# dip.net
KiCad netlist of a schematic drawn in EAGLE
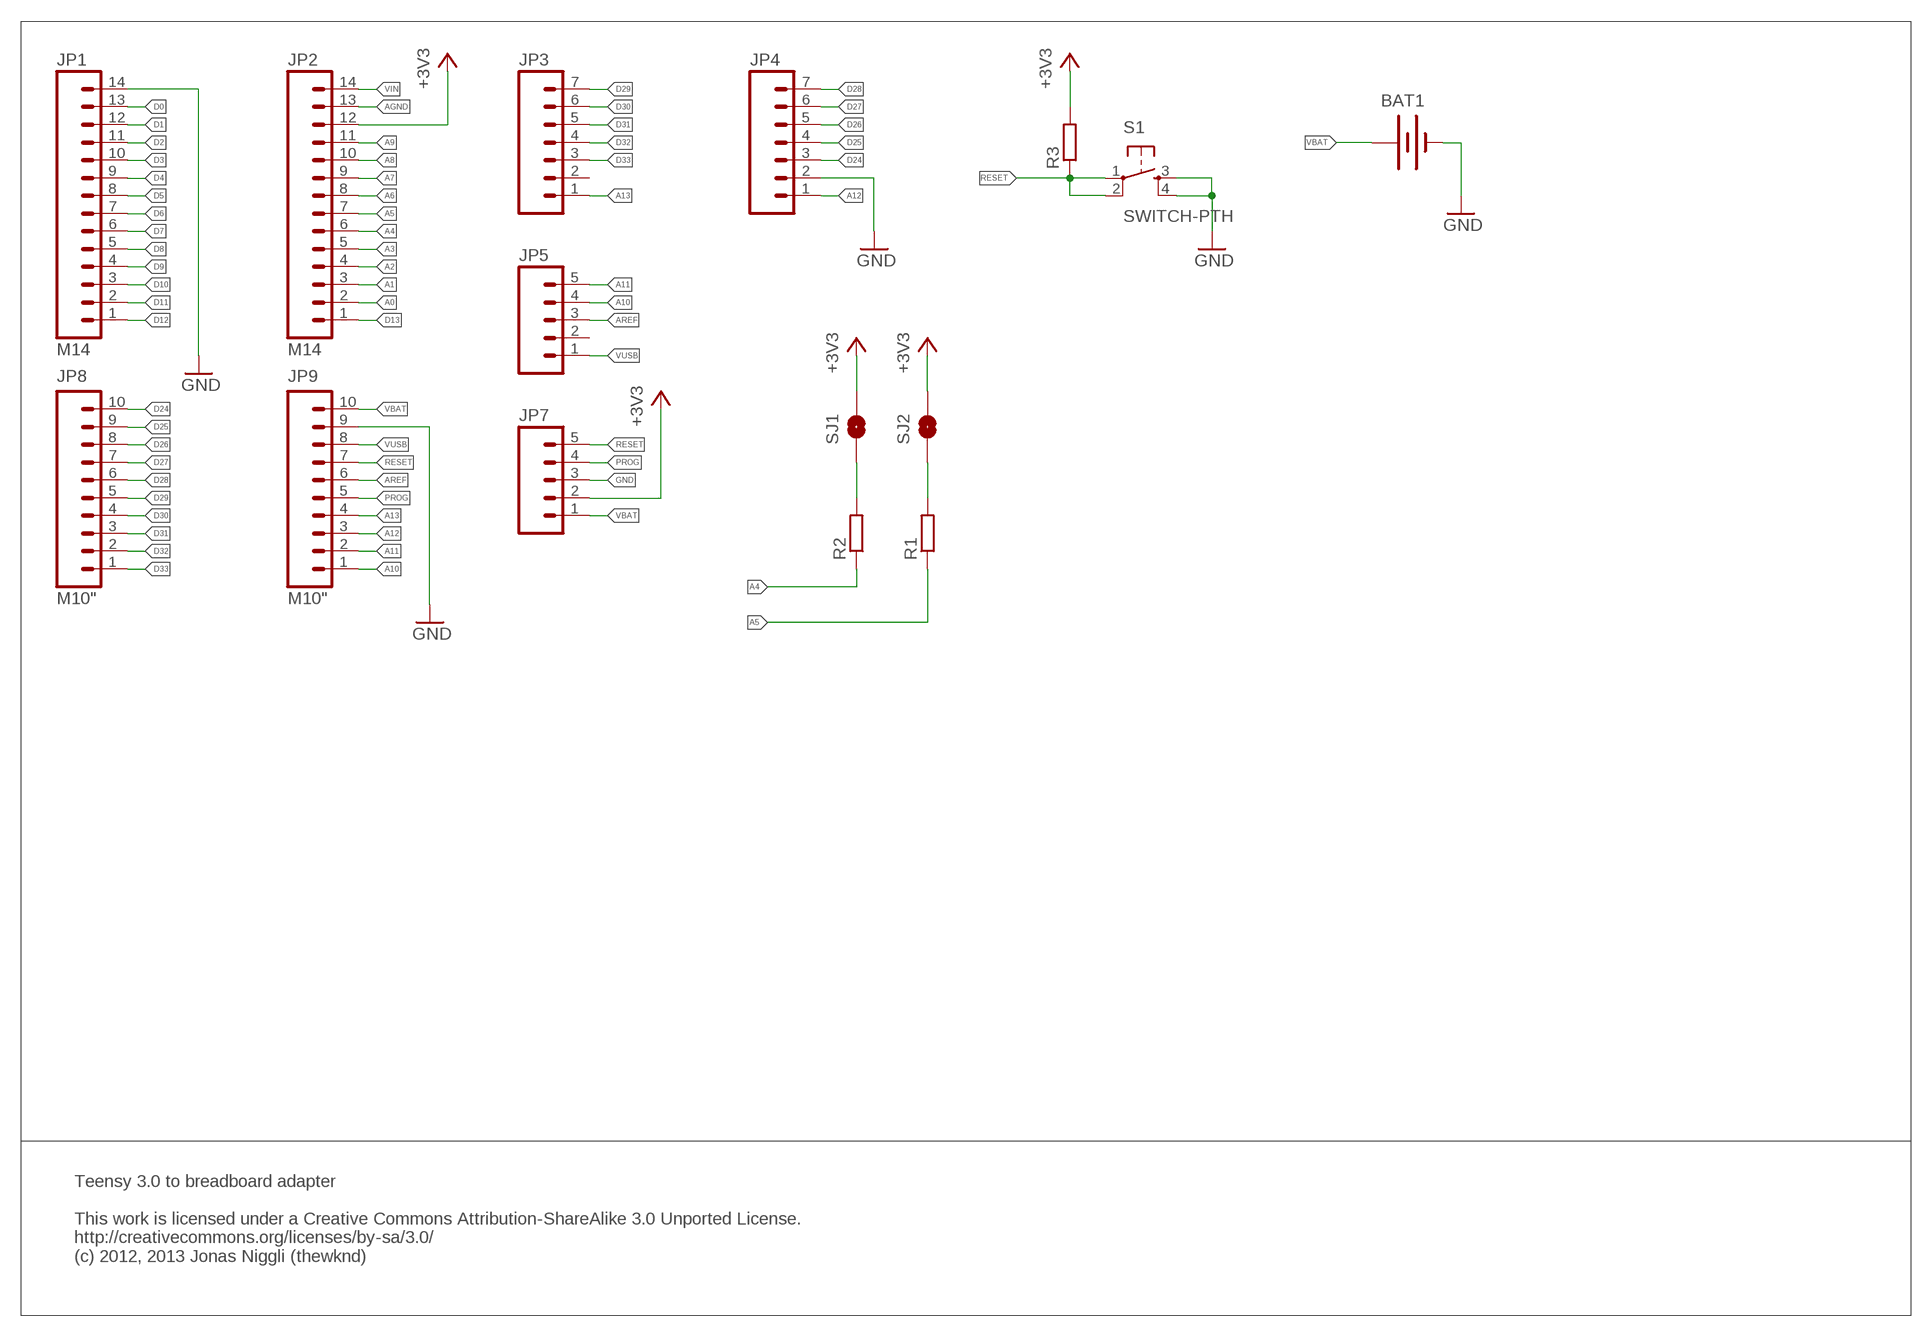
[diagram p0: schematic, sheet 1]

(export (version "E")
  (design (tool "Eeschema 10.0.6"))
  (components
    (comp (ref "BAT1")
      (value "BATTERY12MM")
      (footprint "eagle-import:BATTCON_12MM")
      (libsource (lib "eagle-import") (part "BATTERY12MM"))
    )
    (comp (ref "JP1")
      (value "M14")
      (footprint "eagle-import:1X14")
      (libsource (lib "eagle-import") (part "M14"))
    )
    (comp (ref "JP2")
      (value "M14")
      (footprint "eagle-import:1X14")
      (libsource (lib "eagle-import") (part "M14"))
    )
    (comp (ref "JP3")
      (value "M07")
      (footprint "eagle-import:1X07")
      (libsource (lib "eagle-import") (part "M07"))
    )
    (comp (ref "JP4")
      (value "M07")
      (footprint "eagle-import:1X07")
      (libsource (lib "eagle-import") (part "M07"))
    )
    (comp (ref "JP5")
      (value "M05PTH")
      (footprint "eagle-import:1X05")
      (libsource (lib "eagle-import") (part "M05PTH"))
    )
    (comp (ref "JP7")
      (value "M05PTH")
      (footprint "eagle-import:1X05")
      (libsource (lib "eagle-import") (part "M05PTH"))
    )
    (comp (ref "JP8")
      (value "M10\"")
      (footprint "eagle-import:1X10")
      (libsource (lib "eagle-import") (part "M10{dblquote}"))
    )
    (comp (ref "JP9")
      (value "M10\"")
      (footprint "eagle-import:1X10")
      (libsource (lib "eagle-import") (part "M10{dblquote}"))
    )
    (comp (ref "R1")
      (value "RESISTOR")
      (footprint "eagle-import:R0805")
      (libsource (lib "eagle-import") (part "RESISTOR"))
    )
    (comp (ref "R2")
      (value "RESISTOR")
      (footprint "eagle-import:R0805")
      (libsource (lib "eagle-import") (part "RESISTOR"))
    )
    (comp (ref "R3")
      (value "RESISTOR")
      (footprint "eagle-import:R0805")
      (libsource (lib "eagle-import") (part "RESISTOR"))
    )
    (comp (ref "S1")
      (value "SWITCH-PTH")
      (footprint "eagle-import:SWITCH_PTH")
      (libsource (lib "eagle-import") (part "SWITCH-PTH"))
    )
    (comp (ref "SJ1")
      (value "SOLDERJUMPERNO")
      (footprint "eagle-import:SJ_2S-NO")
      (libsource (lib "eagle-import") (part "SOLDERJUMPERNO"))
    )
    (comp (ref "SJ2")
      (value "SOLDERJUMPERNO")
      (footprint "eagle-import:SJ_2S-NO")
      (libsource (lib "eagle-import") (part "SOLDERJUMPERNO"))
    )
  )
  (nets
    (net (code "1") (name "+3V3") (class "Default")
      (node (ref "JP2") (pin "12") (pinfunction "12_12") (pintype "passive"))
      (node (ref "JP7") (pin "2") (pinfunction "2_2") (pintype "passive"))
      (node (ref "R3") (pin "2") (pinfunction "2_2") (pintype "passive"))
      (node (ref "SJ1") (pin "2") (pinfunction "2_2") (pintype "passive"))
      (node (ref "SJ2") (pin "2") (pinfunction "2_2") (pintype "passive"))
    )
    (net (code "2") (name "A0") (class "Default")
      (node (ref "JP2") (pin "2") (pinfunction "2_2") (pintype "passive"))
    )
    (net (code "3") (name "A1") (class "Default")
      (node (ref "JP2") (pin "3") (pinfunction "3_3") (pintype "passive"))
    )
    (net (code "4") (name "A2") (class "Default")
      (node (ref "JP2") (pin "4") (pinfunction "4_4") (pintype "passive"))
    )
    (net (code "5") (name "A3") (class "Default")
      (node (ref "JP2") (pin "5") (pinfunction "5_5") (pintype "passive"))
    )
    (net (code "6") (name "A4") (class "Default")
      (node (ref "JP2") (pin "6") (pinfunction "6_6") (pintype "passive"))
      (node (ref "R2") (pin "1") (pinfunction "1_1") (pintype "passive"))
    )
    (net (code "7") (name "A5") (class "Default")
      (node (ref "JP2") (pin "7") (pinfunction "7_7") (pintype "passive"))
      (node (ref "R1") (pin "1") (pinfunction "1_1") (pintype "passive"))
    )
    (net (code "8") (name "A6") (class "Default")
      (node (ref "JP2") (pin "8") (pinfunction "8_8") (pintype "passive"))
    )
    (net (code "9") (name "A7") (class "Default")
      (node (ref "JP2") (pin "9") (pinfunction "9_9") (pintype "passive"))
    )
    (net (code "10") (name "A8") (class "Default")
      (node (ref "JP2") (pin "10") (pinfunction "10_10") (pintype "passive"))
    )
    (net (code "11") (name "A9") (class "Default")
      (node (ref "JP2") (pin "11") (pinfunction "11_11") (pintype "passive"))
    )
    (net (code "12") (name "A10") (class "Default")
      (node (ref "JP5") (pin "4") (pinfunction "4_4") (pintype "passive"))
      (node (ref "JP9") (pin "1") (pinfunction "1_1") (pintype "passive"))
    )
    (net (code "13") (name "A11") (class "Default")
      (node (ref "JP5") (pin "5") (pinfunction "5_5") (pintype "passive"))
      (node (ref "JP9") (pin "2") (pinfunction "2_2") (pintype "passive"))
    )
    (net (code "14") (name "A12") (class "Default")
      (node (ref "JP4") (pin "1") (pinfunction "1_1") (pintype "passive"))
      (node (ref "JP9") (pin "3") (pinfunction "3_3") (pintype "passive"))
    )
    (net (code "15") (name "A13") (class "Default")
      (node (ref "JP3") (pin "1") (pinfunction "1_1") (pintype "passive"))
      (node (ref "JP9") (pin "4") (pinfunction "4_4") (pintype "passive"))
    )
    (net (code "16") (name "AGND") (class "Default")
      (node (ref "JP2") (pin "13") (pinfunction "13_13") (pintype "passive"))
    )
    (net (code "17") (name "AREF") (class "Default")
      (node (ref "JP5") (pin "3") (pinfunction "3_3") (pintype "passive"))
      (node (ref "JP9") (pin "6") (pinfunction "6_6") (pintype "passive"))
    )
    (net (code "18") (name "D0") (class "Default")
      (node (ref "JP1") (pin "13") (pinfunction "13_13") (pintype "passive"))
    )
    (net (code "19") (name "D1") (class "Default")
      (node (ref "JP1") (pin "12") (pinfunction "12_12") (pintype "passive"))
    )
    (net (code "20") (name "D2") (class "Default")
      (node (ref "JP1") (pin "11") (pinfunction "11_11") (pintype "passive"))
    )
    (net (code "21") (name "D3") (class "Default")
      (node (ref "JP1") (pin "10") (pinfunction "10_10") (pintype "passive"))
    )
    (net (code "22") (name "D4") (class "Default")
      (node (ref "JP1") (pin "9") (pinfunction "9_9") (pintype "passive"))
    )
    (net (code "23") (name "D5") (class "Default")
      (node (ref "JP1") (pin "8") (pinfunction "8_8") (pintype "passive"))
    )
    (net (code "24") (name "D6") (class "Default")
      (node (ref "JP1") (pin "7") (pinfunction "7_7") (pintype "passive"))
    )
    (net (code "25") (name "D7") (class "Default")
      (node (ref "JP1") (pin "6") (pinfunction "6_6") (pintype "passive"))
    )
    (net (code "26") (name "D8") (class "Default")
      (node (ref "JP1") (pin "5") (pinfunction "5_5") (pintype "passive"))
    )
    (net (code "27") (name "D9") (class "Default")
      (node (ref "JP1") (pin "4") (pinfunction "4_4") (pintype "passive"))
    )
    (net (code "28") (name "D10") (class "Default")
      (node (ref "JP1") (pin "3") (pinfunction "3_3") (pintype "passive"))
    )
    (net (code "29") (name "D11") (class "Default")
      (node (ref "JP1") (pin "2") (pinfunction "2_2") (pintype "passive"))
    )
    (net (code "30") (name "D12") (class "Default")
      (node (ref "JP1") (pin "1") (pinfunction "1_1") (pintype "passive"))
    )
    (net (code "31") (name "D13") (class "Default")
      (node (ref "JP2") (pin "1") (pinfunction "1_1") (pintype "passive"))
    )
    (net (code "32") (name "D24") (class "Default")
      (node (ref "JP4") (pin "3") (pinfunction "3_3") (pintype "passive"))
      (node (ref "JP8") (pin "10") (pinfunction "10_10") (pintype "passive"))
    )
    (net (code "33") (name "D25") (class "Default")
      (node (ref "JP4") (pin "4") (pinfunction "4_4") (pintype "passive"))
      (node (ref "JP8") (pin "9") (pinfunction "9_9") (pintype "passive"))
    )
    (net (code "34") (name "D26") (class "Default")
      (node (ref "JP4") (pin "5") (pinfunction "5_5") (pintype "passive"))
      (node (ref "JP8") (pin "8") (pinfunction "8_8") (pintype "passive"))
    )
    (net (code "35") (name "D27") (class "Default")
      (node (ref "JP4") (pin "6") (pinfunction "6_6") (pintype "passive"))
      (node (ref "JP8") (pin "7") (pinfunction "7_7") (pintype "passive"))
    )
    (net (code "36") (name "D28") (class "Default")
      (node (ref "JP4") (pin "7") (pinfunction "7_7") (pintype "passive"))
      (node (ref "JP8") (pin "6") (pinfunction "6_6") (pintype "passive"))
    )
    (net (code "37") (name "D29") (class "Default")
      (node (ref "JP3") (pin "7") (pinfunction "7_7") (pintype "passive"))
      (node (ref "JP8") (pin "5") (pinfunction "5_5") (pintype "passive"))
    )
    (net (code "38") (name "D30") (class "Default")
      (node (ref "JP3") (pin "6") (pinfunction "6_6") (pintype "passive"))
      (node (ref "JP8") (pin "4") (pinfunction "4_4") (pintype "passive"))
    )
    (net (code "39") (name "D31") (class "Default")
      (node (ref "JP3") (pin "5") (pinfunction "5_5") (pintype "passive"))
      (node (ref "JP8") (pin "3") (pinfunction "3_3") (pintype "passive"))
    )
    (net (code "40") (name "D32") (class "Default")
      (node (ref "JP3") (pin "4") (pinfunction "4_4") (pintype "passive"))
      (node (ref "JP8") (pin "2") (pinfunction "2_2") (pintype "passive"))
    )
    (net (code "41") (name "D33") (class "Default")
      (node (ref "JP3") (pin "3") (pinfunction "3_3") (pintype "passive"))
      (node (ref "JP8") (pin "1") (pinfunction "1_1") (pintype "passive"))
    )
    (net (code "42") (name "GND") (class "Default")
      (node (ref "BAT1") (pin "GND") (pinfunction "-_GND") (pintype "power_in"))
      (node (ref "JP1") (pin "14") (pinfunction "14_14") (pintype "passive"))
      (node (ref "JP4") (pin "2") (pinfunction "2_2") (pintype "passive"))
      (node (ref "JP7") (pin "3") (pinfunction "3_3") (pintype "passive"))
      (node (ref "JP9") (pin "9") (pinfunction "9_9") (pintype "passive"))
      (node (ref "S1") (pin "3") (pinfunction "3_3") (pintype "passive"))
      (node (ref "S1") (pin "4") (pinfunction "4_4") (pintype "passive"))
    )
    (net (code "43") (name "Net-(R1-Pad2)") (class "Default")
      (node (ref "R1") (pin "2") (pinfunction "2_2") (pintype "passive"))
      (node (ref "SJ2") (pin "1") (pinfunction "1_1") (pintype "passive"))
    )
    (net (code "44") (name "Net-(R2-Pad2)") (class "Default")
      (node (ref "R2") (pin "2") (pinfunction "2_2") (pintype "passive"))
      (node (ref "SJ1") (pin "1") (pinfunction "1_1") (pintype "passive"))
    )
    (net (code "45") (name "PROG") (class "Default")
      (node (ref "JP7") (pin "4") (pinfunction "4_4") (pintype "passive"))
      (node (ref "JP9") (pin "5") (pinfunction "5_5") (pintype "passive"))
    )
    (net (code "46") (name "RESET") (class "Default")
      (node (ref "JP7") (pin "5") (pinfunction "5_5") (pintype "passive"))
      (node (ref "JP9") (pin "7") (pinfunction "7_7") (pintype "passive"))
      (node (ref "R3") (pin "1") (pinfunction "1_1") (pintype "passive"))
      (node (ref "S1") (pin "1") (pinfunction "1_1") (pintype "passive"))
      (node (ref "S1") (pin "2") (pinfunction "2_2") (pintype "passive"))
    )
    (net (code "47") (name "VBAT") (class "Default")
      (node (ref "BAT1") (pin "PWR@1") (pinfunction "+_PWR@1") (pintype "power_in"))
      (node (ref "JP7") (pin "1") (pinfunction "1_1") (pintype "passive"))
      (node (ref "JP9") (pin "10") (pinfunction "10_10") (pintype "passive"))
    )
    (net (code "48") (name "VIN") (class "Default")
      (node (ref "JP2") (pin "14") (pinfunction "14_14") (pintype "passive"))
    )
    (net (code "49") (name "VUSB") (class "Default")
      (node (ref "JP5") (pin "1") (pinfunction "1_1") (pintype "passive"))
      (node (ref "JP9") (pin "8") (pinfunction "8_8") (pintype "passive"))
    )
    (net (code "50") (name "unconnected-(JP3-Pad2)") (class "Default")
      (node (ref "JP3") (pin "2") (pinfunction "2_2") (pintype "passive"))
    )
    (net (code "51") (name "unconnected-(JP5-Pad2)") (class "Default")
      (node (ref "JP5") (pin "2") (pinfunction "2_2") (pintype "passive"))
    )
  )
)
